# KRP_SMproject_02.net
KiCad netlist of a schematic drawn in EAGLE
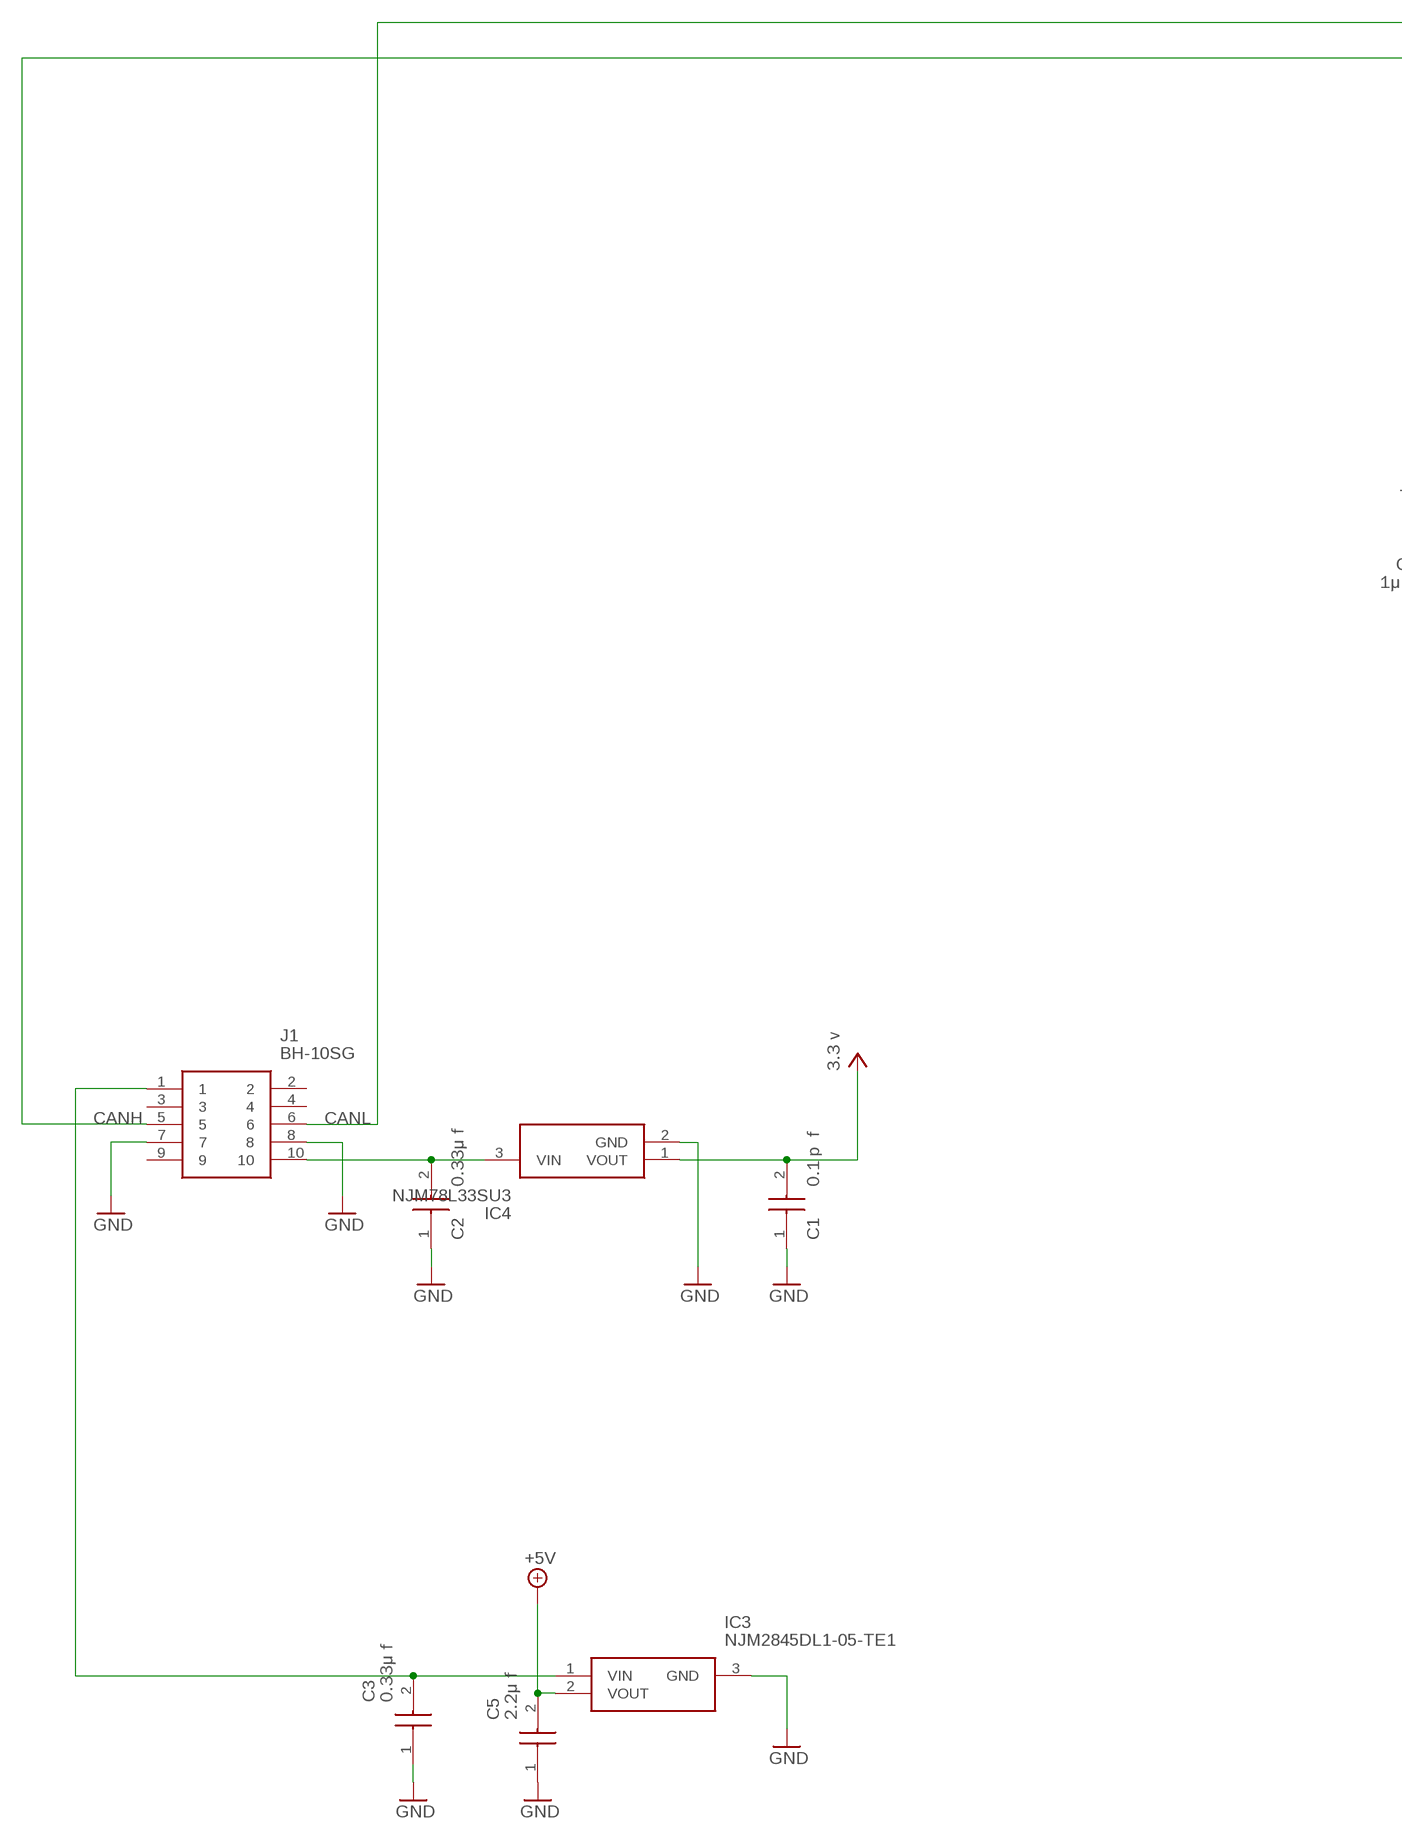
[diagram p0: schematic, sheet 1, part 1 of 2]
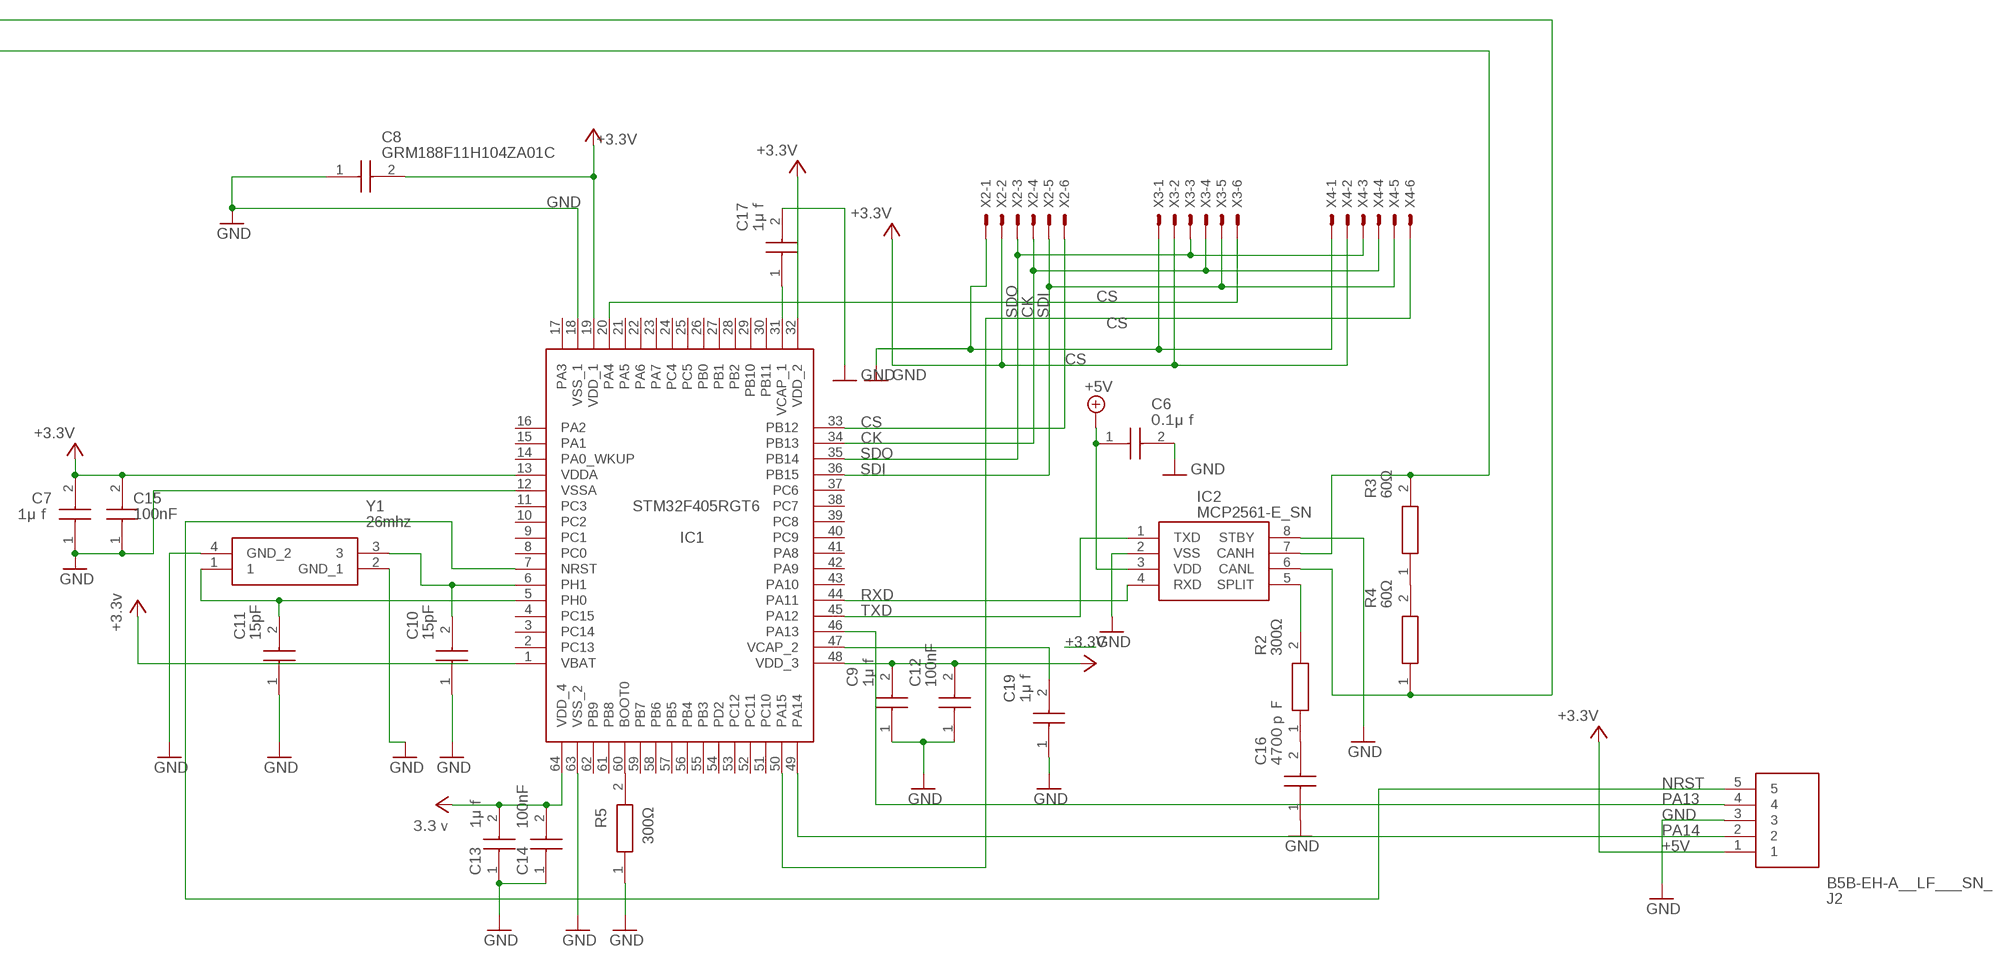
[diagram p1: schematic, sheet 1, part 2 of 2]

(export (version "E")
  (design (tool "Eeschema 10.0.6"))
  (components
    (comp (ref "C1")
      (value "0.1ｐｆ")
      (footprint "eagle-import:CAPC1608X90N")
      (fields (field (name "MANUFACTURER_PART_NUMBER") "GRM188F11H104ZA01C"))
      (libsource (lib "eagle-import") (part "GRM188F11H104ZA01C"))
    )
    (comp (ref "C2")
      (value "0.33μｆ")
      (footprint "eagle-import:CAPC1608X90N")
      (fields (field (name "MANUFACTURER_PART_NUMBER") "GRM188F11H104ZA01C"))
      (libsource (lib "eagle-import") (part "GRM188F11H104ZA01C"))
    )
    (comp (ref "C3")
      (value "0.33μｆ")
      (footprint "eagle-import:CAPC1608X90N")
      (fields (field (name "MANUFACTURER_PART_NUMBER") "GRM188F11H104ZA01C"))
      (libsource (lib "eagle-import") (part "GRM188F11H104ZA01C"))
    )
    (comp (ref "C5")
      (value "2.2μｆ")
      (footprint "eagle-import:CAPC1608X90N")
      (fields (field (name "MANUFACTURER_PART_NUMBER") "GRM188F11H104ZA01C"))
      (libsource (lib "eagle-import") (part "GRM188F11H104ZA01C"))
    )
    (comp (ref "C6")
      (value "0.1μｆ")
      (footprint "eagle-import:CAPC1608X90N")
      (fields (field (name "MANUFACTURER_PART_NUMBER") "GRM188F11H104ZA01C"))
      (libsource (lib "eagle-import") (part "GRM188F11H104ZA01C"))
    )
    (comp (ref "C7")
      (value "1μｆ")
      (footprint "eagle-import:CAPC1608X90N")
      (fields (field (name "MANUFACTURER_PART_NUMBER") "GRM188F11H104ZA01C"))
      (libsource (lib "eagle-import") (part "GRM188F11H104ZA01C"))
    )
    (comp (ref "C8")
      (value "GRM188F11H104ZA01C")
      (footprint "eagle-import:CAPC1608X90N")
      (libsource (lib "eagle-import") (part "GRM188F11H104ZA01C"))
    )
    (comp (ref "C9")
      (value "1μｆ")
      (footprint "eagle-import:CAPC1608X90N")
      (fields (field (name "MANUFACTURER_PART_NUMBER") "GRM188F11H104ZA01C"))
      (libsource (lib "eagle-import") (part "GRM188F11H104ZA01C"))
    )
    (comp (ref "C10")
      (value "15pF")
      (footprint "eagle-import:CAPC1608X90N")
      (fields (field (name "MANUFACTURER_PART_NUMBER") "GRM188F11H104ZA01C"))
      (libsource (lib "eagle-import") (part "GRM188F11H104ZA01C"))
    )
    (comp (ref "C11")
      (value "15pF")
      (footprint "eagle-import:CAPC1608X90N")
      (fields (field (name "MANUFACTURER_PART_NUMBER") "GRM188F11H104ZA01C"))
      (libsource (lib "eagle-import") (part "GRM188F11H104ZA01C"))
    )
    (comp (ref "C12")
      (value "100nF")
      (footprint "eagle-import:CAPC1608X90N")
      (fields (field (name "MANUFACTURER_PART_NUMBER") "GRM188F11H104ZA01C"))
      (libsource (lib "eagle-import") (part "GRM188F11H104ZA01C"))
    )
    (comp (ref "C13")
      (value "1μｆ")
      (footprint "eagle-import:CAPC1608X90N")
      (fields (field (name "MANUFACTURER_PART_NUMBER") "GRM188F11H104ZA01C"))
      (libsource (lib "eagle-import") (part "GRM188F11H104ZA01C"))
    )
    (comp (ref "C14")
      (value "100nF")
      (footprint "eagle-import:CAPC1608X90N")
      (fields (field (name "MANUFACTURER_PART_NUMBER") "GRM188F11H104ZA01C"))
      (libsource (lib "eagle-import") (part "GRM188F11H104ZA01C"))
    )
    (comp (ref "C15")
      (value "100nF")
      (footprint "eagle-import:CAPC1608X90N")
      (fields (field (name "MANUFACTURER_PART_NUMBER") "GRM188F11H104ZA01C"))
      (libsource (lib "eagle-import") (part "GRM188F11H104ZA01C"))
    )
    (comp (ref "C16")
      (value "4700ｐＦ")
      (footprint "eagle-import:CAPC1608X90N")
      (fields (field (name "MANUFACTURER_PART_NUMBER") "GRM188F11H104ZA01C"))
      (libsource (lib "eagle-import") (part "GRM188F11H104ZA01C"))
    )
    (comp (ref "C17")
      (value "1μｆ")
      (footprint "eagle-import:CAPC1608X90N")
      (fields (field (name "MANUFACTURER_PART_NUMBER") "GRM188F11H104ZA01C"))
      (libsource (lib "eagle-import") (part "GRM188F11H104ZA01C"))
    )
    (comp (ref "C19")
      (value "1μｆ")
      (footprint "eagle-import:CAPC1608X90N")
      (fields (field (name "MANUFACTURER_PART_NUMBER") "GRM188F11H104ZA01C"))
      (libsource (lib "eagle-import") (part "GRM188F11H104ZA01C"))
    )
    (comp (ref "IC1")
      (value "STM32F405RGT6")
      (footprint "eagle-import:QFP50P1200X1200X160-64N")
      (fields (field (name "RS_PART_NUMBER") "7468217P"))
      (libsource (lib "eagle-import") (part "STM32F405RGT6"))
    )
    (comp (ref "IC2")
      (value "MCP2561-E_SN")
      (footprint "eagle-import:SOIC127P600X175-8N")
      (fields
        (field (name "MANUFACTURER_PART_NUMBER") "MCP2561-E/SN")
        (field (name "RS_PART_NUMBER") "7990216P")
      )
      (libsource (lib "eagle-import") (part "MCP2561-E_SN"))
    )
    (comp (ref "IC3")
      (value "NJM2845DL1-05-TE1")
      (footprint "eagle-import:TO-252-3-L1")
      (libsource (lib "eagle-import") (part "NJM2845DL1-05-TE1"))
    )
    (comp (ref "IC4")
      (value "NJM78L33SU3")
      (footprint "eagle-import:SOT-89-3")
      (libsource (lib "eagle-import") (part "NJM78L33SU3"))
    )
    (comp (ref "J1")
      (value "BH-10SG")
      (footprint "eagle-import:SHDR10W64P254_2X5_2032X910X935")
      (libsource (lib "eagle-import") (part "BH-10SG"))
    )
    (comp (ref "J2")
      (value "B5B-EH-A__LF___SN_")
      (footprint "eagle-import:SHDR5W64P0X250_1X5_1500X380X60")
      (fields
        (field (name "MANUFACTURER_PART_NUMBER") "B5B-EH-A (LF) (SN)")
        (field (name "RS_PART_NUMBER") "5151412P")
      )
      (libsource (lib "eagle-import") (part "B5B-EH-A__LF___SN_"))
    )
    (comp (ref "R2")
      (value "300Ω")
      (footprint "eagle-import:RESC1608X50N")
      (fields
        (field (name "MANUFACTURER_PART_NUMBER") "RG1608N-101-W-T1")
        (field (name "RS_PART_NUMBER") "0160452")
      )
      (libsource (lib "eagle-import") (part "RG1608N-101-W-T1"))
    )
    (comp (ref "R3")
      (value "60Ω")
      (footprint "eagle-import:RESC1608X50N")
      (fields
        (field (name "MANUFACTURER_PART_NUMBER") "RG1608N-101-W-T1")
        (field (name "RS_PART_NUMBER") "0160452")
      )
      (libsource (lib "eagle-import") (part "RG1608N-101-W-T1"))
    )
    (comp (ref "R4")
      (value "60Ω")
      (footprint "eagle-import:RESC1608X50N")
      (fields
        (field (name "MANUFACTURER_PART_NUMBER") "RG1608N-101-W-T1")
        (field (name "RS_PART_NUMBER") "0160452")
      )
      (libsource (lib "eagle-import") (part "RG1608N-101-W-T1"))
    )
    (comp (ref "R5")
      (value "300Ω")
      (footprint "eagle-import:RESC1608X50N")
      (fields
        (field (name "MANUFACTURER_PART_NUMBER") "RG1608N-101-W-T1")
        (field (name "RS_PART_NUMBER") "0160452")
      )
      (libsource (lib "eagle-import") (part "RG1608N-101-W-T1"))
    )
    (comp (ref "X2")
      (value "22-23-2061")
      (footprint "eagle-import:22-23-2061")
      (fields (field (name "MF") "MOLEX"))
      (libsource (lib "eagle-import") (part "22-23-2061"))
    )
    (comp (ref "X3")
      (value "22-23-2061")
      (footprint "eagle-import:22-23-2061")
      (fields (field (name "MF") "MOLEX"))
      (libsource (lib "eagle-import") (part "22-23-2061"))
    )
    (comp (ref "X4")
      (value "22-23-2061")
      (footprint "eagle-import:22-23-2061")
      (fields (field (name "MF") "MOLEX"))
      (libsource (lib "eagle-import") (part "22-23-2061"))
    )
    (comp (ref "Y1")
      (value "26mhz")
      (footprint "eagle-import:FA128")
      (fields (field (name "MANUFACTURER_PART_NUMBER") "FA-128 32.0000MF20X-K3"))
      (libsource (lib "eagle-import") (part "FA-128_32.0000MF20X-K3"))
    )
  )
  (nets
    (net (code "1") (name "+3.3V") (class "Default")
      (node (ref "C1") (pin "2") (pinfunction "2_2") (pintype "bidirectional"))
      (node (ref "C12") (pin "2") (pinfunction "2_2") (pintype "bidirectional"))
      (node (ref "C13") (pin "2") (pinfunction "2_2") (pintype "bidirectional"))
      (node (ref "C14") (pin "2") (pinfunction "2_2") (pintype "bidirectional"))
      (node (ref "C15") (pin "2") (pinfunction "2_2") (pintype "bidirectional"))
      (node (ref "C5") (pin "2") (pinfunction "2_2") (pintype "bidirectional"))
      (node (ref "C6") (pin "1") (pinfunction "1_1") (pintype "bidirectional"))
      (node (ref "C7") (pin "2") (pinfunction "2_2") (pintype "bidirectional"))
      (node (ref "C8") (pin "2") (pinfunction "2_2") (pintype "bidirectional"))
      (node (ref "C9") (pin "2") (pinfunction "2_2") (pintype "bidirectional"))
      (node (ref "IC1") (pin "1") (pinfunction "VBAT_1") (pintype "bidirectional"))
      (node (ref "IC1") (pin "13") (pinfunction "VDDA_13") (pintype "power_in"))
      (node (ref "IC1") (pin "19") (pinfunction "VDD_1_19") (pintype "power_in"))
      (node (ref "IC1") (pin "32") (pinfunction "VDD_2_32") (pintype "power_in"))
      (node (ref "IC1") (pin "48") (pinfunction "VDD_3_48") (pintype "power_in"))
      (node (ref "IC1") (pin "64") (pinfunction "VDD_4_64") (pintype "power_in"))
      (node (ref "IC2") (pin "3") (pinfunction "VDD_3") (pintype "bidirectional"))
      (node (ref "IC3") (pin "2") (pinfunction "VOUT_2") (pintype "bidirectional"))
      (node (ref "IC4") (pin "1") (pinfunction "VOUT_1") (pintype "bidirectional"))
      (node (ref "J2") (pin "1") (pinfunction "1_1") (pintype "bidirectional"))
      (node (ref "X2") (pin "2") (pinfunction "S_2") (pintype "passive"))
      (node (ref "X3") (pin "2") (pinfunction "S_2") (pintype "passive"))
      (node (ref "X4") (pin "2") (pinfunction "S_2") (pintype "passive"))
    )
    (net (code "2") (name "/CANH") (class "Default")
      (node (ref "IC2") (pin "7") (pinfunction "CANH_7") (pintype "bidirectional"))
      (node (ref "J1") (pin "5") (pinfunction "5_5") (pintype "bidirectional"))
      (node (ref "R3") (pin "2") (pinfunction "2_2") (pintype "bidirectional"))
    )
    (net (code "3") (name "/CANL") (class "Default")
      (node (ref "IC2") (pin "6") (pinfunction "CANL_6") (pintype "bidirectional"))
      (node (ref "J1") (pin "6") (pinfunction "6_6") (pintype "bidirectional"))
      (node (ref "R4") (pin "1") (pinfunction "1_1") (pintype "bidirectional"))
    )
    (net (code "4") (name "/CK") (class "Default")
      (node (ref "IC1") (pin "34") (pinfunction "PB13_34") (pintype "bidirectional"))
      (node (ref "X2") (pin "4") (pinfunction "S_4") (pintype "passive"))
      (node (ref "X3") (pin "4") (pinfunction "S_4") (pintype "passive"))
      (node (ref "X4") (pin "4") (pinfunction "S_4") (pintype "passive"))
    )
    (net (code "5") (name "/CS") (class "Default")
      (node (ref "IC1") (pin "20") (pinfunction "PA4_20") (pintype "bidirectional"))
      (node (ref "IC1") (pin "33") (pinfunction "PB12_33") (pintype "bidirectional"))
      (node (ref "IC1") (pin "50") (pinfunction "PA15_50") (pintype "bidirectional"))
      (node (ref "X2") (pin "6") (pinfunction "S_6") (pintype "passive"))
      (node (ref "X3") (pin "6") (pinfunction "S_6") (pintype "passive"))
      (node (ref "X4") (pin "6") (pinfunction "S_6") (pintype "passive"))
    )
    (net (code "6") (name "/NRST") (class "Default")
      (node (ref "IC1") (pin "7") (pinfunction "NRST_7") (pintype "input"))
      (node (ref "J2") (pin "5") (pinfunction "5_5") (pintype "bidirectional"))
    )
    (net (code "7") (name "/PA13") (class "Default")
      (node (ref "IC1") (pin "46") (pinfunction "PA13_46") (pintype "bidirectional"))
      (node (ref "J2") (pin "4") (pinfunction "4_4") (pintype "bidirectional"))
    )
    (net (code "8") (name "/PA14") (class "Default")
      (node (ref "IC1") (pin "49") (pinfunction "PA14_49") (pintype "bidirectional"))
      (node (ref "J2") (pin "2") (pinfunction "2_2") (pintype "bidirectional"))
    )
    (net (code "9") (name "/RXD") (class "Default")
      (node (ref "IC1") (pin "44") (pinfunction "PA11_44") (pintype "bidirectional"))
      (node (ref "IC2") (pin "4") (pinfunction "RXD_4") (pintype "bidirectional"))
    )
    (net (code "10") (name "/SDI") (class "Default")
      (node (ref "IC1") (pin "36") (pinfunction "PB15_36") (pintype "bidirectional"))
      (node (ref "X2") (pin "5") (pinfunction "S_5") (pintype "passive"))
      (node (ref "X3") (pin "5") (pinfunction "S_5") (pintype "passive"))
      (node (ref "X4") (pin "5") (pinfunction "S_5") (pintype "passive"))
    )
    (net (code "11") (name "/SDO") (class "Default")
      (node (ref "IC1") (pin "35") (pinfunction "PB14_35") (pintype "bidirectional"))
      (node (ref "X2") (pin "3") (pinfunction "S_3") (pintype "passive"))
      (node (ref "X3") (pin "3") (pinfunction "S_3") (pintype "passive"))
      (node (ref "X4") (pin "3") (pinfunction "S_3") (pintype "passive"))
    )
    (net (code "12") (name "/TXD") (class "Default")
      (node (ref "IC1") (pin "45") (pinfunction "PA12_45") (pintype "bidirectional"))
      (node (ref "IC2") (pin "1") (pinfunction "TXD_1") (pintype "bidirectional"))
    )
    (net (code "13") (name "GND") (class "Default")
      (node (ref "C1") (pin "1") (pinfunction "1_1") (pintype "bidirectional"))
      (node (ref "C10") (pin "1") (pinfunction "1_1") (pintype "bidirectional"))
      (node (ref "C11") (pin "1") (pinfunction "1_1") (pintype "bidirectional"))
      (node (ref "C12") (pin "1") (pinfunction "1_1") (pintype "bidirectional"))
      (node (ref "C13") (pin "1") (pinfunction "1_1") (pintype "bidirectional"))
      (node (ref "C14") (pin "1") (pinfunction "1_1") (pintype "bidirectional"))
      (node (ref "C15") (pin "1") (pinfunction "1_1") (pintype "bidirectional"))
      (node (ref "C16") (pin "1") (pinfunction "1_1") (pintype "bidirectional"))
      (node (ref "C17") (pin "2") (pinfunction "2_2") (pintype "bidirectional"))
      (node (ref "C19") (pin "1") (pinfunction "1_1") (pintype "bidirectional"))
      (node (ref "C2") (pin "1") (pinfunction "1_1") (pintype "bidirectional"))
      (node (ref "C3") (pin "1") (pinfunction "1_1") (pintype "bidirectional"))
      (node (ref "C5") (pin "1") (pinfunction "1_1") (pintype "bidirectional"))
      (node (ref "C6") (pin "2") (pinfunction "2_2") (pintype "bidirectional"))
      (node (ref "C7") (pin "1") (pinfunction "1_1") (pintype "bidirectional"))
      (node (ref "C8") (pin "1") (pinfunction "1_1") (pintype "bidirectional"))
      (node (ref "C9") (pin "1") (pinfunction "1_1") (pintype "bidirectional"))
      (node (ref "IC1") (pin "12") (pinfunction "VSSA_12") (pintype "power_in"))
      (node (ref "IC1") (pin "18") (pinfunction "VSS_1_18") (pintype "power_in"))
      (node (ref "IC1") (pin "63") (pinfunction "VSS_2_63") (pintype "power_in"))
      (node (ref "IC2") (pin "2") (pinfunction "VSS_2") (pintype "bidirectional"))
      (node (ref "IC2") (pin "8") (pinfunction "STBY_8") (pintype "bidirectional"))
      (node (ref "IC3") (pin "3") (pinfunction "GND_3") (pintype "bidirectional"))
      (node (ref "IC4") (pin "2") (pinfunction "GND_2") (pintype "bidirectional"))
      (node (ref "J1") (pin "7") (pinfunction "7_7") (pintype "bidirectional"))
      (node (ref "J1") (pin "8") (pinfunction "8_8") (pintype "bidirectional"))
      (node (ref "J2") (pin "3") (pinfunction "3_3") (pintype "bidirectional"))
      (node (ref "R5") (pin "1") (pinfunction "1_1") (pintype "bidirectional"))
      (node (ref "X2") (pin "1") (pinfunction "S_1") (pintype "passive"))
      (node (ref "X3") (pin "1") (pinfunction "S_1") (pintype "passive"))
      (node (ref "X4") (pin "1") (pinfunction "S_1") (pintype "passive"))
      (node (ref "Y1") (pin "2") (pinfunction "GND_1_2") (pintype "bidirectional"))
      (node (ref "Y1") (pin "4") (pinfunction "GND_2_4") (pintype "bidirectional"))
    )
    (net (code "14") (name "Net-(C16-Pad2)") (class "Default")
      (node (ref "C16") (pin "2") (pinfunction "2_2") (pintype "bidirectional"))
      (node (ref "R2") (pin "1") (pinfunction "1_1") (pintype "bidirectional"))
    )
    (net (code "15") (name "Net-(IC1-BOOT0)") (class "Default")
      (node (ref "IC1") (pin "60") (pinfunction "BOOT0_60") (pintype "bidirectional"))
      (node (ref "R5") (pin "2") (pinfunction "2_2") (pintype "bidirectional"))
    )
    (net (code "16") (name "Net-(IC1-PH0)") (class "Default")
      (node (ref "C11") (pin "2") (pinfunction "2_2") (pintype "bidirectional"))
      (node (ref "IC1") (pin "5") (pinfunction "PH0_5") (pintype "bidirectional"))
      (node (ref "Y1") (pin "1") (pinfunction "1_1") (pintype "bidirectional"))
    )
    (net (code "17") (name "Net-(IC1-PH1)") (class "Default")
      (node (ref "C10") (pin "2") (pinfunction "2_2") (pintype "bidirectional"))
      (node (ref "IC1") (pin "6") (pinfunction "PH1_6") (pintype "bidirectional"))
      (node (ref "Y1") (pin "3") (pinfunction "3_3") (pintype "bidirectional"))
    )
    (net (code "18") (name "Net-(IC1-VCAP_1)") (class "Default")
      (node (ref "C17") (pin "1") (pinfunction "1_1") (pintype "bidirectional"))
      (node (ref "IC1") (pin "31") (pinfunction "VCAP_1_31") (pintype "bidirectional"))
    )
    (net (code "19") (name "Net-(IC1-VCAP_2)") (class "Default")
      (node (ref "C19") (pin "2") (pinfunction "2_2") (pintype "bidirectional"))
      (node (ref "IC1") (pin "47") (pinfunction "VCAP_2_47") (pintype "bidirectional"))
    )
    (net (code "20") (name "Net-(IC2-SPLIT)") (class "Default")
      (node (ref "IC2") (pin "5") (pinfunction "SPLIT_5") (pintype "bidirectional"))
      (node (ref "R2") (pin "2") (pinfunction "2_2") (pintype "bidirectional"))
    )
    (net (code "21") (name "Net-(IC3-VIN)") (class "Default")
      (node (ref "C3") (pin "2") (pinfunction "2_2") (pintype "bidirectional"))
      (node (ref "IC3") (pin "1") (pinfunction "VIN_1") (pintype "bidirectional"))
      (node (ref "J1") (pin "1") (pinfunction "1_1") (pintype "bidirectional"))
    )
    (net (code "22") (name "Net-(IC4-VIN)") (class "Default")
      (node (ref "C2") (pin "2") (pinfunction "2_2") (pintype "bidirectional"))
      (node (ref "IC4") (pin "3") (pinfunction "VIN_3") (pintype "bidirectional"))
      (node (ref "J1") (pin "10") (pinfunction "10_10") (pintype "bidirectional"))
    )
    (net (code "23") (name "Net-(R3-Pad1)") (class "Default")
      (node (ref "R3") (pin "1") (pinfunction "1_1") (pintype "bidirectional"))
      (node (ref "R4") (pin "2") (pinfunction "2_2") (pintype "bidirectional"))
    )
    (net (code "24") (name "unconnected-(IC1-PA0_WKUP-Pad14)") (class "Default")
      (node (ref "IC1") (pin "14") (pinfunction "PA0_WKUP_14") (pintype "bidirectional"))
    )
    (net (code "25") (name "unconnected-(IC1-PA1-Pad15)") (class "Default")
      (node (ref "IC1") (pin "15") (pinfunction "PA1_15") (pintype "bidirectional"))
    )
    (net (code "26") (name "unconnected-(IC1-PA2-Pad16)") (class "Default")
      (node (ref "IC1") (pin "16") (pinfunction "PA2_16") (pintype "bidirectional"))
    )
    (net (code "27") (name "unconnected-(IC1-PA3-Pad17)") (class "Default")
      (node (ref "IC1") (pin "17") (pinfunction "PA3_17") (pintype "bidirectional"))
    )
    (net (code "28") (name "unconnected-(IC1-PA5-Pad21)") (class "Default")
      (node (ref "IC1") (pin "21") (pinfunction "PA5_21") (pintype "bidirectional"))
    )
    (net (code "29") (name "unconnected-(IC1-PA6-Pad22)") (class "Default")
      (node (ref "IC1") (pin "22") (pinfunction "PA6_22") (pintype "bidirectional"))
    )
    (net (code "30") (name "unconnected-(IC1-PA7-Pad23)") (class "Default")
      (node (ref "IC1") (pin "23") (pinfunction "PA7_23") (pintype "bidirectional"))
    )
    (net (code "31") (name "unconnected-(IC1-PA8-Pad41)") (class "Default")
      (node (ref "IC1") (pin "41") (pinfunction "PA8_41") (pintype "bidirectional"))
    )
    (net (code "32") (name "unconnected-(IC1-PA9-Pad42)") (class "Default")
      (node (ref "IC1") (pin "42") (pinfunction "PA9_42") (pintype "bidirectional"))
    )
    (net (code "33") (name "unconnected-(IC1-PA10-Pad43)") (class "Default")
      (node (ref "IC1") (pin "43") (pinfunction "PA10_43") (pintype "bidirectional"))
    )
    (net (code "34") (name "unconnected-(IC1-PB0-Pad26)") (class "Default")
      (node (ref "IC1") (pin "26") (pinfunction "PB0_26") (pintype "bidirectional"))
    )
    (net (code "35") (name "unconnected-(IC1-PB1-Pad27)") (class "Default")
      (node (ref "IC1") (pin "27") (pinfunction "PB1_27") (pintype "bidirectional"))
    )
    (net (code "36") (name "unconnected-(IC1-PB2-Pad28)") (class "Default")
      (node (ref "IC1") (pin "28") (pinfunction "PB2_28") (pintype "bidirectional"))
    )
    (net (code "37") (name "unconnected-(IC1-PB3-Pad55)") (class "Default")
      (node (ref "IC1") (pin "55") (pinfunction "PB3_55") (pintype "bidirectional"))
    )
    (net (code "38") (name "unconnected-(IC1-PB4-Pad56)") (class "Default")
      (node (ref "IC1") (pin "56") (pinfunction "PB4_56") (pintype "bidirectional"))
    )
    (net (code "39") (name "unconnected-(IC1-PB5-Pad57)") (class "Default")
      (node (ref "IC1") (pin "57") (pinfunction "PB5_57") (pintype "bidirectional"))
    )
    (net (code "40") (name "unconnected-(IC1-PB6-Pad58)") (class "Default")
      (node (ref "IC1") (pin "58") (pinfunction "PB6_58") (pintype "bidirectional"))
    )
    (net (code "41") (name "unconnected-(IC1-PB7-Pad59)") (class "Default")
      (node (ref "IC1") (pin "59") (pinfunction "PB7_59") (pintype "bidirectional"))
    )
    (net (code "42") (name "unconnected-(IC1-PB8-Pad61)") (class "Default")
      (node (ref "IC1") (pin "61") (pinfunction "PB8_61") (pintype "bidirectional"))
    )
    (net (code "43") (name "unconnected-(IC1-PB9-Pad62)") (class "Default")
      (node (ref "IC1") (pin "62") (pinfunction "PB9_62") (pintype "bidirectional"))
    )
    (net (code "44") (name "unconnected-(IC1-PB10-Pad29)") (class "Default")
      (node (ref "IC1") (pin "29") (pinfunction "PB10_29") (pintype "bidirectional"))
    )
    (net (code "45") (name "unconnected-(IC1-PB11-Pad30)") (class "Default")
      (node (ref "IC1") (pin "30") (pinfunction "PB11_30") (pintype "bidirectional"))
    )
    (net (code "46") (name "unconnected-(IC1-PC0-Pad8)") (class "Default")
      (node (ref "IC1") (pin "8") (pinfunction "PC0_8") (pintype "bidirectional"))
    )
    (net (code "47") (name "unconnected-(IC1-PC1-Pad9)") (class "Default")
      (node (ref "IC1") (pin "9") (pinfunction "PC1_9") (pintype "bidirectional"))
    )
    (net (code "48") (name "unconnected-(IC1-PC2-Pad10)") (class "Default")
      (node (ref "IC1") (pin "10") (pinfunction "PC2_10") (pintype "bidirectional"))
    )
    (net (code "49") (name "unconnected-(IC1-PC3-Pad11)") (class "Default")
      (node (ref "IC1") (pin "11") (pinfunction "PC3_11") (pintype "bidirectional"))
    )
    (net (code "50") (name "unconnected-(IC1-PC4-Pad24)") (class "Default")
      (node (ref "IC1") (pin "24") (pinfunction "PC4_24") (pintype "bidirectional"))
    )
    (net (code "51") (name "unconnected-(IC1-PC5-Pad25)") (class "Default")
      (node (ref "IC1") (pin "25") (pinfunction "PC5_25") (pintype "bidirectional"))
    )
    (net (code "52") (name "unconnected-(IC1-PC6-Pad37)") (class "Default")
      (node (ref "IC1") (pin "37") (pinfunction "PC6_37") (pintype "bidirectional"))
    )
    (net (code "53") (name "unconnected-(IC1-PC7-Pad38)") (class "Default")
      (node (ref "IC1") (pin "38") (pinfunction "PC7_38") (pintype "bidirectional"))
    )
    (net (code "54") (name "unconnected-(IC1-PC8-Pad39)") (class "Default")
      (node (ref "IC1") (pin "39") (pinfunction "PC8_39") (pintype "bidirectional"))
    )
    (net (code "55") (name "unconnected-(IC1-PC9-Pad40)") (class "Default")
      (node (ref "IC1") (pin "40") (pinfunction "PC9_40") (pintype "bidirectional"))
    )
    (net (code "56") (name "unconnected-(IC1-PC10-Pad51)") (class "Default")
      (node (ref "IC1") (pin "51") (pinfunction "PC10_51") (pintype "bidirectional"))
    )
    (net (code "57") (name "unconnected-(IC1-PC11-Pad52)") (class "Default")
      (node (ref "IC1") (pin "52") (pinfunction "PC11_52") (pintype "bidirectional"))
    )
    (net (code "58") (name "unconnected-(IC1-PC12-Pad53)") (class "Default")
      (node (ref "IC1") (pin "53") (pinfunction "PC12_53") (pintype "bidirectional"))
    )
    (net (code "59") (name "unconnected-(IC1-PC13-Pad2)") (class "Default")
      (node (ref "IC1") (pin "2") (pinfunction "PC13_2") (pintype "bidirectional"))
    )
    (net (code "60") (name "unconnected-(IC1-PC14-Pad3)") (class "Default")
      (node (ref "IC1") (pin "3") (pinfunction "PC14_3") (pintype "bidirectional"))
    )
    (net (code "61") (name "unconnected-(IC1-PC15-Pad4)") (class "Default")
      (node (ref "IC1") (pin "4") (pinfunction "PC15_4") (pintype "bidirectional"))
    )
    (net (code "62") (name "unconnected-(IC1-PD2-Pad54)") (class "Default")
      (node (ref "IC1") (pin "54") (pinfunction "PD2_54") (pintype "bidirectional"))
    )
    (net (code "63") (name "unconnected-(J1-Pad2)") (class "Default")
      (node (ref "J1") (pin "2") (pinfunction "2_2") (pintype "bidirectional"))
    )
    (net (code "64") (name "unconnected-(J1-Pad3)") (class "Default")
      (node (ref "J1") (pin "3") (pinfunction "3_3") (pintype "bidirectional"))
    )
    (net (code "65") (name "unconnected-(J1-Pad4)") (class "Default")
      (node (ref "J1") (pin "4") (pinfunction "4_4") (pintype "bidirectional"))
    )
    (net (code "66") (name "unconnected-(J1-Pad9)") (class "Default")
      (node (ref "J1") (pin "9") (pinfunction "9_9") (pintype "bidirectional"))
    )
  )
)
